# StepDown.net
KiCad netlist of a schematic drawn in EAGLE
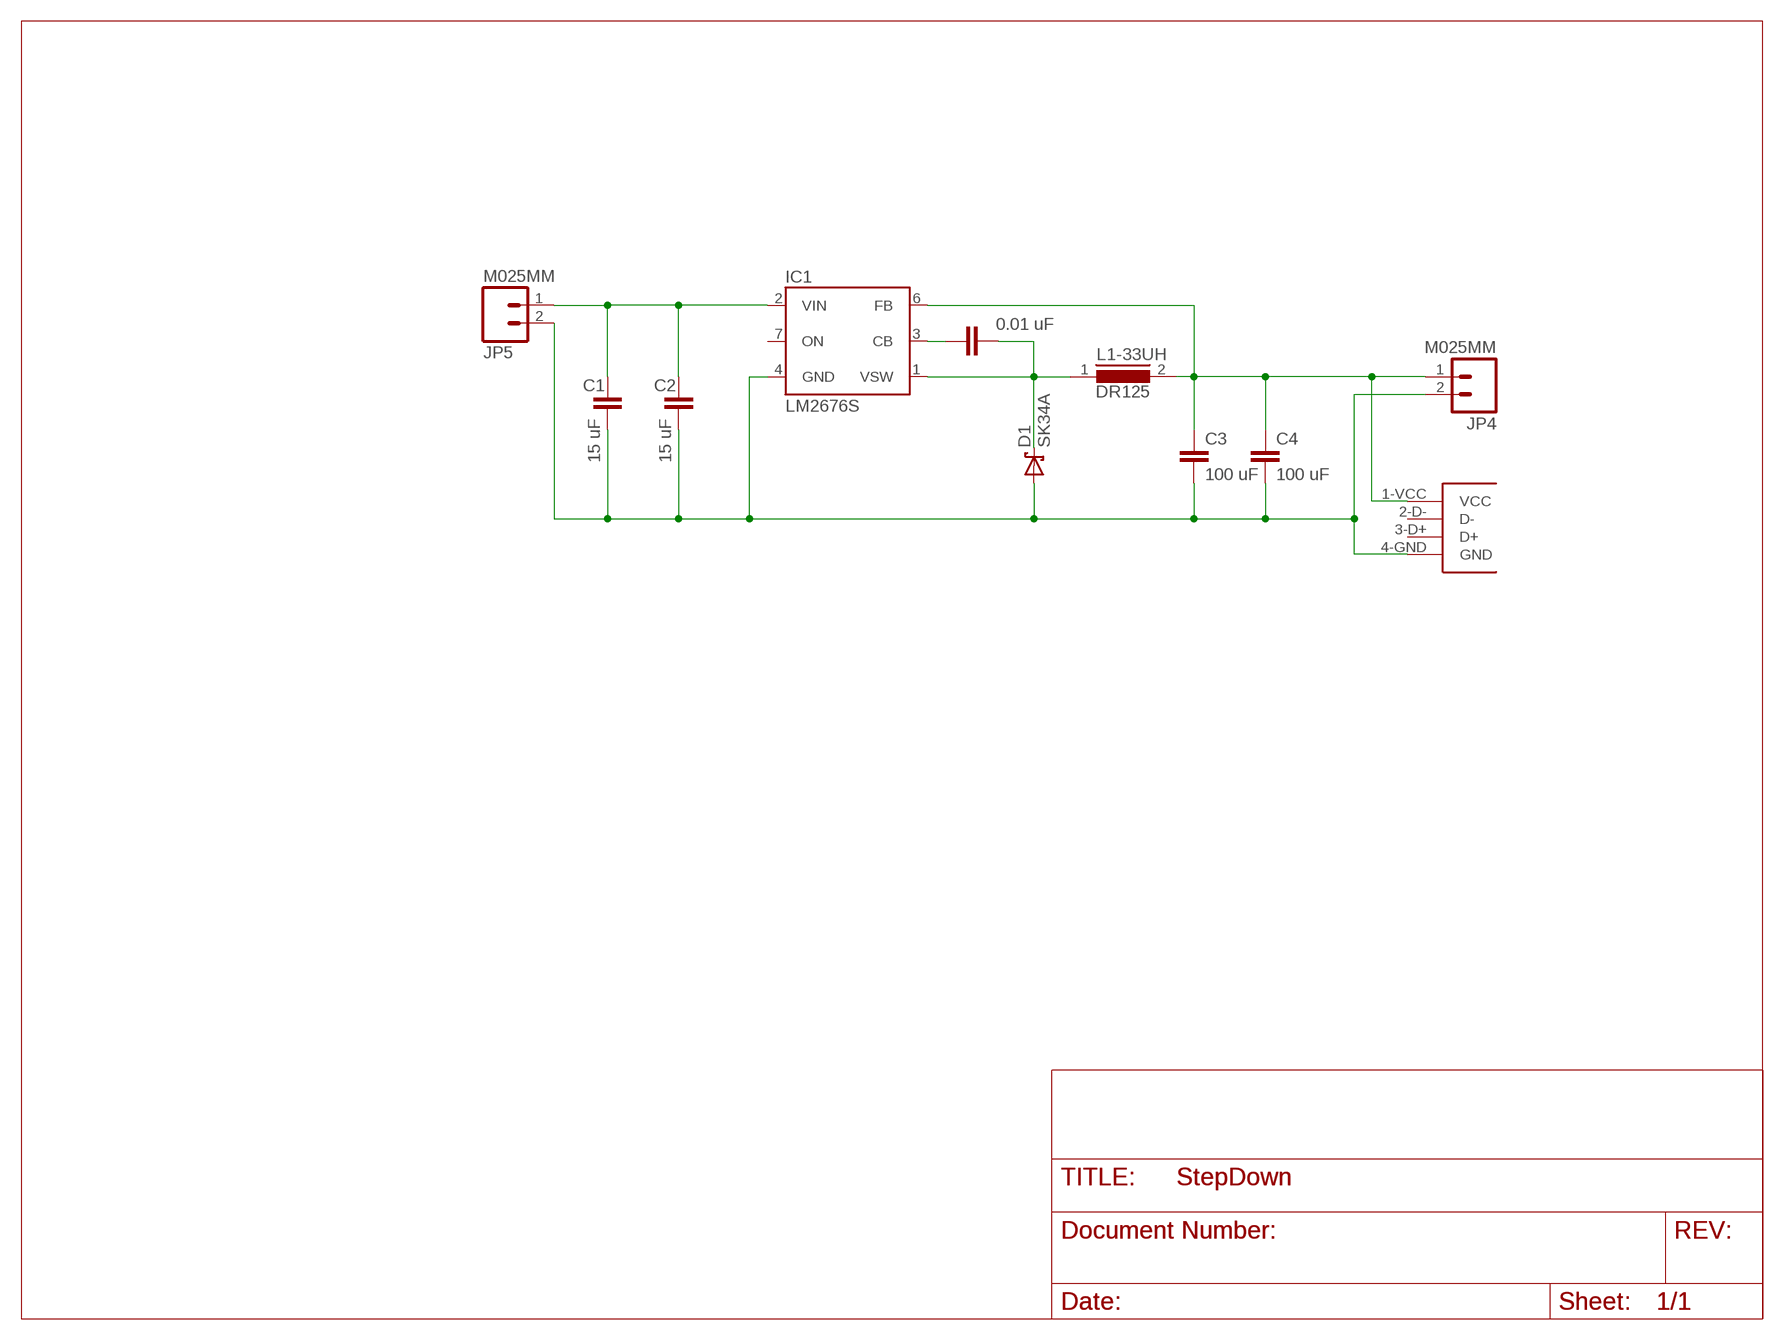
[diagram p0: schematic, sheet 1]

(export (version "E")
  (design (tool "Eeschema 10.0.6"))
  (components
    (comp (ref "C1")
      (value "15 uF")
      (footprint "eagle-import:C1210")
      (libsource (lib "eagle-import") (part "C-EUC1210"))
    )
    (comp (ref "C2")
      (value "15 uF")
      (footprint "eagle-import:C1210")
      (libsource (lib "eagle-import") (part "C-EUC1210"))
    )
    (comp (ref "C3")
      (value "100 uF")
      (footprint "eagle-import:C1210")
      (libsource (lib "eagle-import") (part "C-EUC1210"))
    )
    (comp (ref "C4")
      (value "100 uF")
      (footprint "eagle-import:C1210")
      (libsource (lib "eagle-import") (part "C-EUC1210"))
    )
    (comp (ref "C6")
      (value "0.01 uF")
      (footprint "eagle-import:0805")
      (libsource (lib "eagle-import") (part "1.0UF-25V-+80/-20(0805)"))
    )
    (comp (ref "D1")
      (value "SK34A")
      (footprint "eagle-import:DO214AA")
      (libsource (lib "eagle-import") (part "SK34A"))
    )
    (comp (ref "IC1")
      (value "LM2676S")
      (footprint "eagle-import:TO263-7")
      (libsource (lib "eagle-import") (part "LM2676S"))
    )
    (comp (ref "JP4")
      (value "M025MM")
      (footprint "eagle-import:SCREWTERMINAL-5MM-2")
      (libsource (lib "eagle-import") (part "M025MM"))
    )
    (comp (ref "JP5")
      (value "M025MM")
      (footprint "eagle-import:SCREWTERMINAL-5MM-2")
      (libsource (lib "eagle-import") (part "M025MM"))
    )
    (comp (ref "L1-33UH")
      (value "DR125")
      (footprint "eagle-import:DR125")
      (libsource (lib "eagle-import") (part "DR125"))
    )
    (comp (ref "U$1")
      (value "87520-USB-A-FEMALE")
      (footprint "eagle-import:87520-USB-A-FEMALE")
      (libsource (lib "eagle-import") (part "87520-USB-A-FEMALE"))
    )
  )
  (nets
    (net (code "1") (name "Net-(IC1-CB)") (class "Default")
      (node (ref "C6") (pin "1") (pinfunction "1_1") (pintype "passive"))
      (node (ref "IC1") (pin "3") (pinfunction "CB_3") (pintype "input"))
    )
    (net (code "2") (name "Net-(IC1-FB)") (class "Default")
      (node (ref "C3") (pin "1") (pinfunction "1_1") (pintype "passive"))
      (node (ref "C4") (pin "1") (pinfunction "1_1") (pintype "passive"))
      (node (ref "IC1") (pin "6") (pinfunction "FB_6") (pintype "input"))
      (node (ref "JP4") (pin "1") (pinfunction "1_1") (pintype "passive"))
      (node (ref "L1-33UH") (pin "2") (pinfunction "2_2") (pintype "passive"))
      (node (ref "U$1") (pin "1-VCC") (pinfunction "VCC_1-VCC") (pintype "power_in"))
    )
    (net (code "3") (name "Net-(IC1-GND)") (class "Default")
      (node (ref "C1") (pin "2") (pinfunction "2_2") (pintype "passive"))
      (node (ref "C2") (pin "2") (pinfunction "2_2") (pintype "passive"))
      (node (ref "C3") (pin "2") (pinfunction "2_2") (pintype "passive"))
      (node (ref "C4") (pin "2") (pinfunction "2_2") (pintype "passive"))
      (node (ref "D1") (pin "A") (pinfunction "A_A") (pintype "passive"))
      (node (ref "IC1") (pin "4") (pinfunction "GND_4") (pintype "power_in"))
      (node (ref "JP4") (pin "2") (pinfunction "2_2") (pintype "passive"))
      (node (ref "JP5") (pin "2") (pinfunction "2_2") (pintype "passive"))
      (node (ref "U$1") (pin "4-GND") (pinfunction "GND_4-GND") (pintype "power_in"))
    )
    (net (code "4") (name "Net-(IC1-VIN)") (class "Default")
      (node (ref "C1") (pin "1") (pinfunction "1_1") (pintype "passive"))
      (node (ref "C2") (pin "1") (pinfunction "1_1") (pintype "passive"))
      (node (ref "IC1") (pin "2") (pinfunction "VIN_2") (pintype "power_in"))
      (node (ref "JP5") (pin "1") (pinfunction "1_1") (pintype "passive"))
    )
    (net (code "5") (name "Net-(IC1-VSW)") (class "Default")
      (node (ref "C6") (pin "2") (pinfunction "2_2") (pintype "passive"))
      (node (ref "D1") (pin "C") (pinfunction "C_C") (pintype "passive"))
      (node (ref "IC1") (pin "1") (pinfunction "VSW_1") (pintype "output"))
      (node (ref "L1-33UH") (pin "1") (pinfunction "1_1") (pintype "passive"))
    )
    (net (code "6") (name "unconnected-(IC1-ON-Pad7)") (class "Default")
      (node (ref "IC1") (pin "7") (pinfunction "ON_7") (pintype "passive"))
    )
    (net (code "7") (name "unconnected-(U$1-D+-Pad3-D+)") (class "Default")
      (node (ref "U$1") (pin "3-D+") (pinfunction "D+_3-D+") (pintype "bidirectional"))
    )
    (net (code "8") (name "unconnected-(U$1-D--Pad2-D-)") (class "Default")
      (node (ref "U$1") (pin "2-D-") (pinfunction "D-_2-D-") (pintype "bidirectional"))
    )
  )
)
